# LPCB235_-_ASI_RS485.net
KiCad netlist of a schematic drawn in Altium Designer
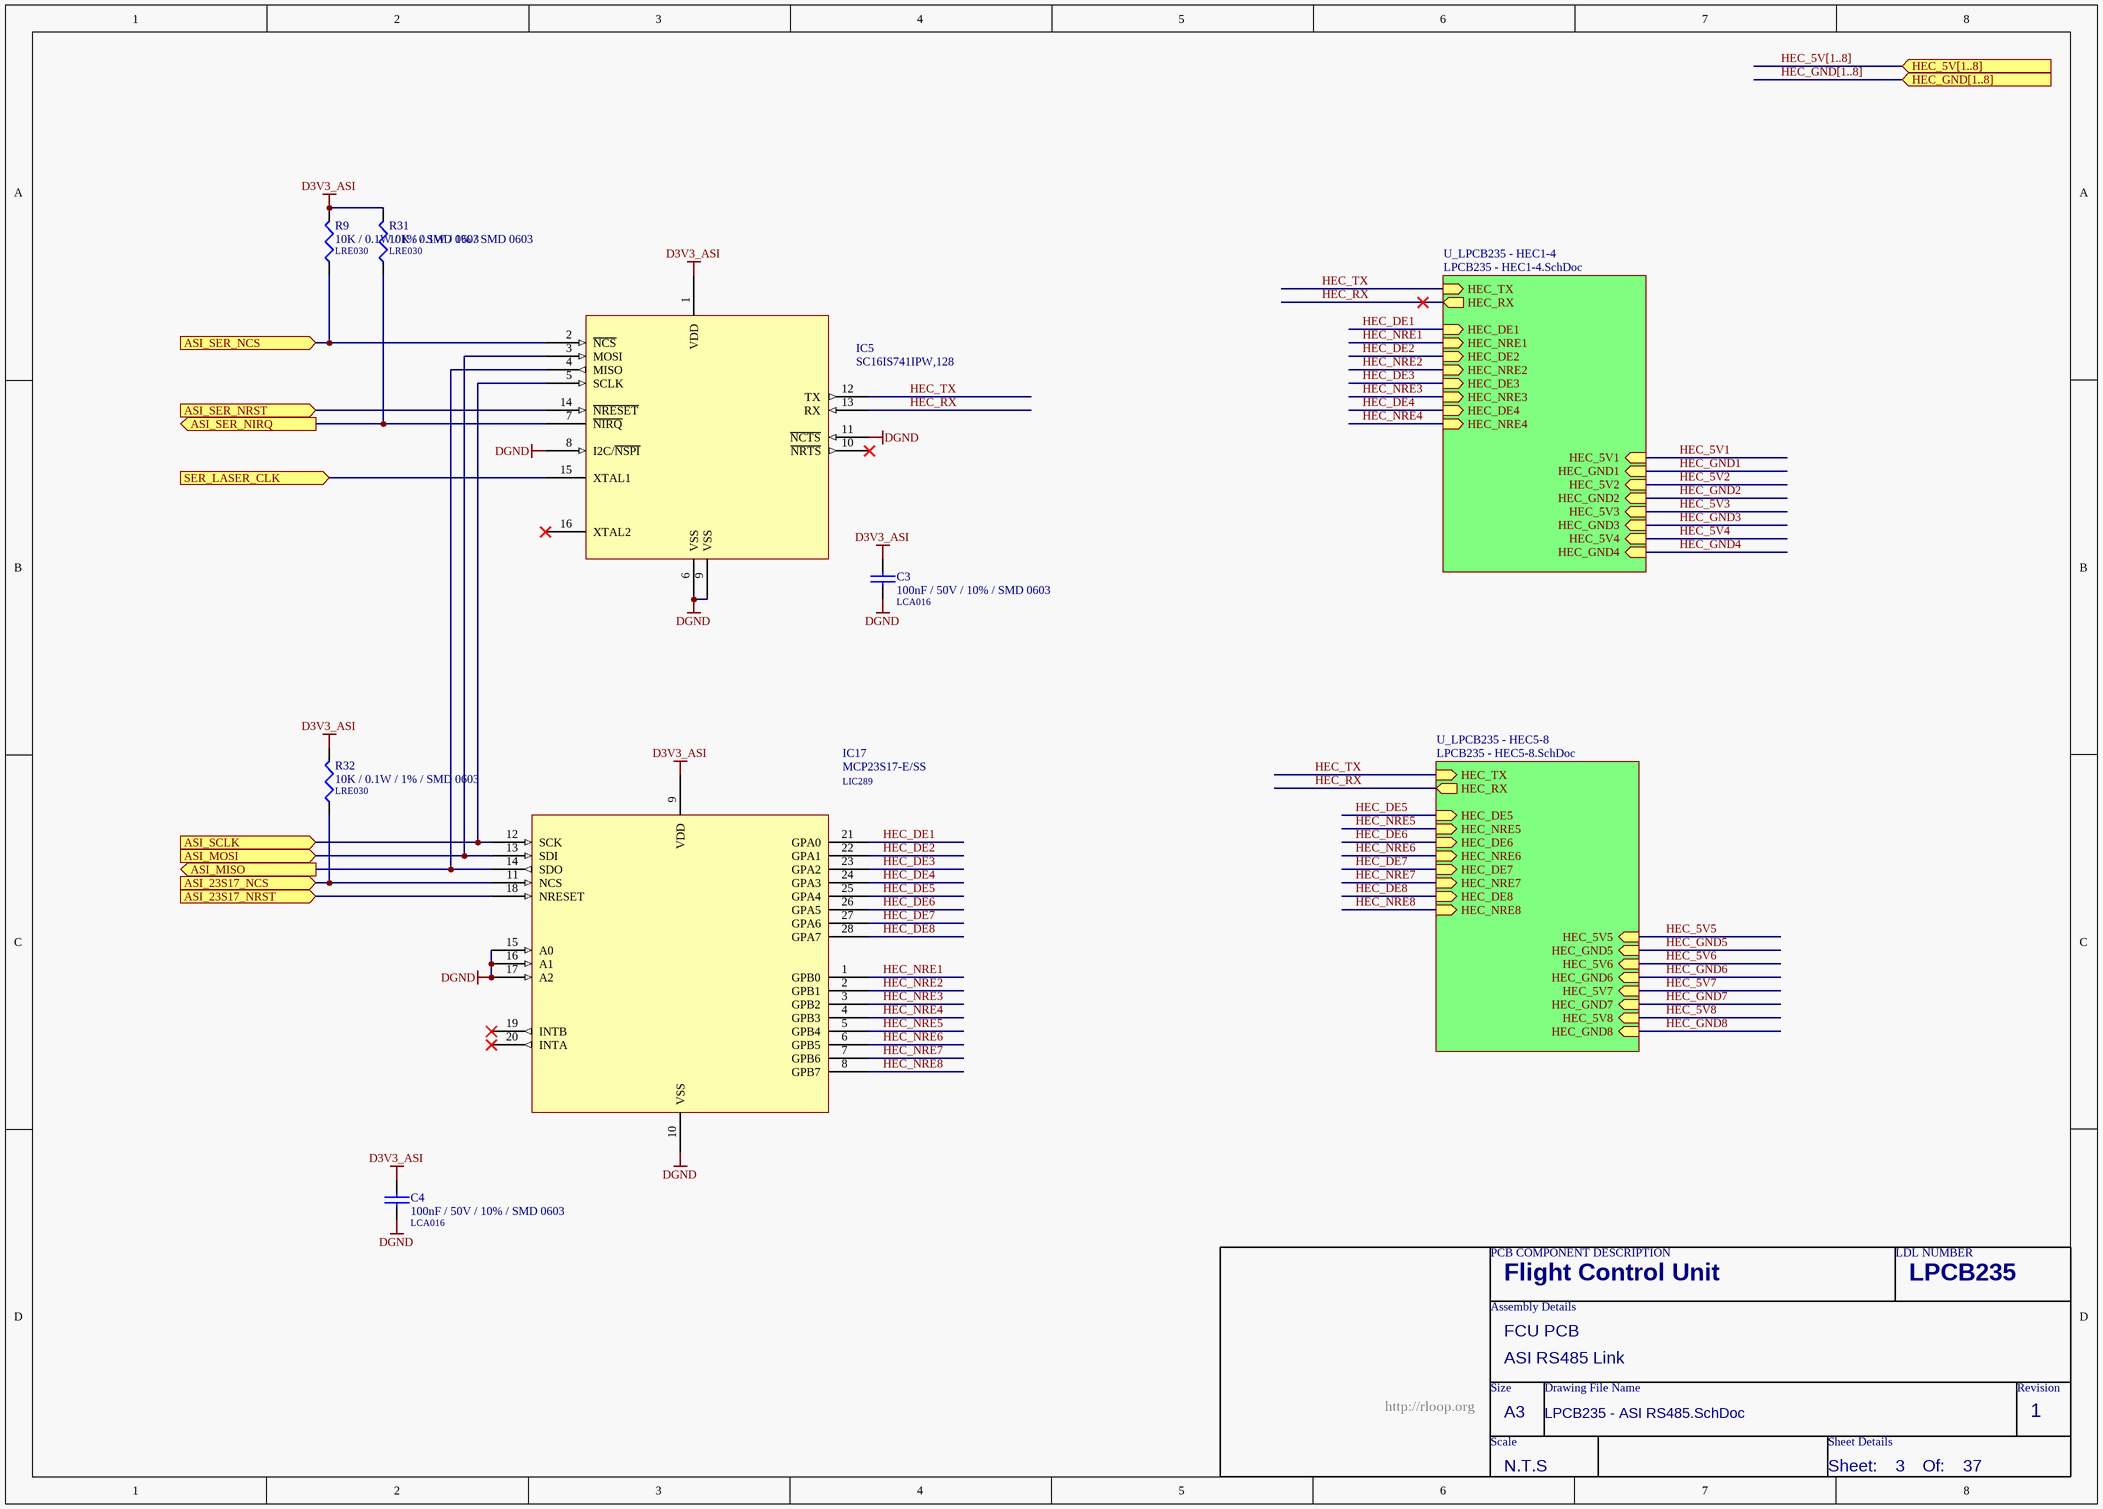
[diagram p0: LPCB235 - ASI RS485.SchDoc]

(export (version "E")
  (design (tool "Eeschema 10.0.6"))
  (components
    (comp (ref "C3")
      (value "100nF / 50V / 10% / SMD 0603")
      (footprint "LFP011__CC1608-0603-IPC7351_B")
      (description "Capacitor, Ceramic Chip, 100nF (0.1uF), 50V, 5%, SMD 0603 [LCA016]")
      (fields (field (name "LDL_NUMBER") "LCA016"))
      (libsource (lib "LDL_Capacitors") (part "100nF / 50V / 10% / SMD 0603"))
    )
    (comp (ref "C4")
      (value "100nF / 50V / 10% / SMD 0603")
      (footprint "LFP011__CC1608-0603-IPC7351_B")
      (description "Capacitor, Ceramic Chip, 100nF (0.1uF), 50V, 5%, SMD 0603 [LCA016]")
      (fields (field (name "LDL_NUMBER") "LCA016"))
      (libsource (lib "LDL_Capacitors") (part "100nF / 50V / 10% / SMD 0603"))
    )
    (comp (ref "IC5")
      (value "SC16IS741IPW,128")
      (footprint "LFP049__TSSOP-16")
      (description "IC, SPI to UART bridge [LIC472]")
      (libsource (lib "LDL_Semiconductors") (part "SC16IS741IPW,128"))
    )
    (comp (ref "IC17")
      (value "MCP23S17-E/SS")
      (footprint "LFP050__SSOP28")
      (description "IC, SPI IO Expander, 16bit, SMD SSOP28 [LIC289]")
      (fields (field (name "LDL_NUMBER") "LIC289"))
      (libsource (lib "LDL_Semiconductors") (part "MCP23S17-E/SS"))
    )
    (comp (ref "R9")
      (value "10K / 0.1W / 1% / SMD 0603")
      (footprint "LFP020__CR1608-0603-IPC7351_B")
      (description "Resistor, Ceramic Chip, 10K, 0.1W, 1%, SMD 0603 [LRE030]")
      (fields (field (name "LDL_NUMBER") "LRE030"))
      (libsource (lib "LDL_Resistors") (part "10K / 0.1W / 1% / SMD 0603"))
    )
    (comp (ref "R31")
      (value "10K / 0.1W / 1% / SMD 0603")
      (footprint "LFP020__CR1608-0603-IPC7351_B")
      (description "Resistor, Ceramic Chip, 10K, 0.1W, 1%, SMD 0603 [LRE030]")
      (fields (field (name "LDL_NUMBER") "LRE030"))
      (libsource (lib "LDL_Resistors") (part "10K / 0.1W / 1% / SMD 0603"))
    )
    (comp (ref "R32")
      (value "10K / 0.1W / 1% / SMD 0603")
      (footprint "LFP020__CR1608-0603-IPC7351_B")
      (description "Resistor, Ceramic Chip, 10K, 0.1W, 1%, SMD 0603 [LRE030]")
      (fields (field (name "LDL_NUMBER") "LRE030"))
      (libsource (lib "LDL_Resistors") (part "10K / 0.1W / 1% / SMD 0603"))
    )
  )
  (nets
    (net (code "1") (name "/ASI_23S17_NCS") (class "Default")
      (node (ref "IC17") (pin "11") (pinfunction "NCS_11") (pintype "input"))
      (node (ref "R32") (pin "1") (pintype "passive"))
    )
    (net (code "2") (name "/ASI_23S17_NRST") (class "Default")
      (node (ref "IC17") (pin "18") (pinfunction "NRESET_18") (pintype "input"))
    )
    (net (code "3") (name "/ASI_MISO") (class "Default")
      (node (ref "IC17") (pin "14") (pinfunction "SDO_14") (pintype "output"))
      (node (ref "IC5") (pin "4") (pinfunction "MISO_4") (pintype "output"))
    )
    (net (code "4") (name "/ASI_MOSI") (class "Default")
      (node (ref "IC17") (pin "13") (pinfunction "SDI_13") (pintype "input"))
      (node (ref "IC5") (pin "3") (pinfunction "MOSI_3") (pintype "input"))
    )
    (net (code "5") (name "/ASI_SCLK") (class "Default")
      (node (ref "IC17") (pin "12") (pinfunction "SCK_12") (pintype "input"))
      (node (ref "IC5") (pin "5") (pinfunction "SCLK_5") (pintype "input"))
    )
    (net (code "6") (name "/ASI_SER_NCS") (class "Default")
      (node (ref "IC5") (pin "2") (pinfunction "~{NCS}_2") (pintype "input"))
      (node (ref "R9") (pin "1") (pintype "passive"))
    )
    (net (code "7") (name "/ASI_SER_NIRQ") (class "Default")
      (node (ref "IC5") (pin "7") (pinfunction "~{NIRQ}_7") (pintype "passive"))
      (node (ref "R31") (pin "1") (pintype "passive"))
    )
    (net (code "8") (name "/ASI_SER_NRST") (class "Default")
      (node (ref "IC5") (pin "14") (pinfunction "~{NRESET}_14") (pintype "input"))
    )
    (net (code "18") (name "/HEC_DE1") (class "Default")
      (node (ref "IC17") (pin "21") (pinfunction "GPA0_21") (pintype "passive"))
    )
    (net (code "19") (name "/HEC_DE2") (class "Default")
      (node (ref "IC17") (pin "22") (pinfunction "GPA1_22") (pintype "passive"))
    )
    (net (code "20") (name "/HEC_DE3") (class "Default")
      (node (ref "IC17") (pin "23") (pinfunction "GPA2_23") (pintype "passive"))
    )
    (net (code "21") (name "/HEC_DE4") (class "Default")
      (node (ref "IC17") (pin "24") (pinfunction "GPA3_24") (pintype "passive"))
    )
    (net (code "22") (name "/HEC_DE5") (class "Default")
      (node (ref "IC17") (pin "25") (pinfunction "GPA4_25") (pintype "passive"))
    )
    (net (code "23") (name "/HEC_DE6") (class "Default")
      (node (ref "IC17") (pin "26") (pinfunction "GPA5_26") (pintype "passive"))
    )
    (net (code "24") (name "/HEC_DE7") (class "Default")
      (node (ref "IC17") (pin "27") (pinfunction "GPA6_27") (pintype "passive"))
    )
    (net (code "25") (name "/HEC_DE8") (class "Default")
      (node (ref "IC17") (pin "28") (pinfunction "GPA7_28") (pintype "passive"))
    )
    (net (code "35") (name "/HEC_NRE1") (class "Default")
      (node (ref "IC17") (pin "1") (pinfunction "GPB0_1") (pintype "passive"))
    )
    (net (code "36") (name "/HEC_NRE2") (class "Default")
      (node (ref "IC17") (pin "2") (pinfunction "GPB1_2") (pintype "passive"))
    )
    (net (code "37") (name "/HEC_NRE3") (class "Default")
      (node (ref "IC17") (pin "3") (pinfunction "GPB2_3") (pintype "passive"))
    )
    (net (code "38") (name "/HEC_NRE4") (class "Default")
      (node (ref "IC17") (pin "4") (pinfunction "GPB3_4") (pintype "passive"))
    )
    (net (code "39") (name "/HEC_NRE5") (class "Default")
      (node (ref "IC17") (pin "5") (pinfunction "GPB4_5") (pintype "passive"))
    )
    (net (code "40") (name "/HEC_NRE6") (class "Default")
      (node (ref "IC17") (pin "6") (pinfunction "GPB5_6") (pintype "passive"))
    )
    (net (code "41") (name "/HEC_NRE7") (class "Default")
      (node (ref "IC17") (pin "7") (pinfunction "GPB6_7") (pintype "passive"))
    )
    (net (code "42") (name "/HEC_NRE8") (class "Default")
      (node (ref "IC17") (pin "8") (pinfunction "GPB7_8") (pintype "passive"))
    )
    (net (code "43") (name "/HEC_RX") (class "Default")
      (node (ref "IC5") (pin "13") (pinfunction "RX_13") (pintype "input"))
    )
    (net (code "44") (name "/HEC_TX") (class "Default")
      (node (ref "IC5") (pin "12") (pinfunction "TX_12") (pintype "output"))
    )
    (net (code "45") (name "/SER_LASER_CLK") (class "Default")
      (node (ref "IC5") (pin "15") (pinfunction "XTAL1_15") (pintype "passive"))
    )
    (net (code "46") (name "D3V3_ASI") (class "Default")
      (node (ref "C3") (pin "1") (pintype "passive"))
      (node (ref "C4") (pin "1") (pintype "passive"))
      (node (ref "IC17") (pin "9") (pinfunction "VDD_9") (pintype "power_in"))
      (node (ref "IC5") (pin "1") (pinfunction "VDD_1") (pintype "power_in"))
      (node (ref "R31") (pin "2") (pintype "passive"))
      (node (ref "R32") (pin "2") (pintype "passive"))
      (node (ref "R9") (pin "2") (pintype "passive"))
    )
    (net (code "47") (name "DGND") (class "Default")
      (node (ref "C3") (pin "2") (pintype "passive"))
      (node (ref "C4") (pin "2") (pintype "passive"))
      (node (ref "IC17") (pin "10") (pinfunction "VSS_10") (pintype "power_in"))
      (node (ref "IC17") (pin "15") (pinfunction "A0_15") (pintype "input"))
      (node (ref "IC17") (pin "16") (pinfunction "A1_16") (pintype "input"))
      (node (ref "IC17") (pin "17") (pinfunction "A2_17") (pintype "input"))
      (node (ref "IC5") (pin "11") (pinfunction "~{NCTS}_11") (pintype "input"))
      (node (ref "IC5") (pin "6") (pinfunction "VSS_6") (pintype "power_in"))
      (node (ref "IC5") (pin "8") (pinfunction "I2C/~{NSPI}_8") (pintype "input"))
      (node (ref "IC5") (pin "9") (pinfunction "VSS_9") (pintype "power_in"))
    )
    (net (code "48") (name "unconnected-(IC5-XTAL2-Pad16)") (class "Default")
      (node (ref "IC5") (pin "16") (pinfunction "XTAL2_16") (pintype "passive+no_connect"))
    )
    (net (code "49") (name "unconnected-(IC5-~{NRTS}-Pad10)") (class "Default")
      (node (ref "IC5") (pin "10") (pinfunction "~{NRTS}_10") (pintype "output+no_connect"))
    )
    (net (code "50") (name "unconnected-(IC17-INTA-Pad20)") (class "Default")
      (node (ref "IC17") (pin "20") (pinfunction "INTA_20") (pintype "output+no_connect"))
    )
    (net (code "51") (name "unconnected-(IC17-INTB-Pad19)") (class "Default")
      (node (ref "IC17") (pin "19") (pinfunction "INTB_19") (pintype "output+no_connect"))
    )
  )
)
